# FrontPanel.net
KiCad netlist of a schematic drawn in EAGLE
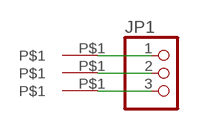
[diagram p0: schematic, sheet 1]

(export (version "E")
  (design (tool "Eeschema 10.0.6"))
  (components
    (comp (ref "JP1")
      (value "PINHD-1X3_2.54-SMD")
      (footprint "eagle-import:1X03SMD")
      (libsource (lib "eagle-import") (part "PINHD-1X3_2.54-SMD"))
    )
    (comp (ref "U$8")
      (value "TOUCHPAD")
      (footprint "eagle-import:TOUCH_FIELD_10X5")
      (libsource (lib "eagle-import") (part "TOUCHPAD"))
    )
    (comp (ref "U$9")
      (value "TOUCHPAD")
      (footprint "eagle-import:TOUCH_FIELD_10X5")
      (libsource (lib "eagle-import") (part "TOUCHPAD"))
    )
    (comp (ref "U$10")
      (value "TOUCHPAD")
      (footprint "eagle-import:TOUCH_FIELD_10X5")
      (libsource (lib "eagle-import") (part "TOUCHPAD"))
    )
  )
  (nets
    (net (code "1") (name "Net-(JP1-Pad1)") (class "Default")
      (node (ref "JP1") (pin "1") (pinfunction "1_1") (pintype "passive"))
      (node (ref "U$8") (pin "P$1") (pinfunction "P$1_P$1") (pintype "bidirectional"))
    )
    (net (code "2") (name "Net-(JP1-Pad2)") (class "Default")
      (node (ref "JP1") (pin "2") (pinfunction "2_2") (pintype "passive"))
      (node (ref "U$9") (pin "P$1") (pinfunction "P$1_P$1") (pintype "bidirectional"))
    )
    (net (code "3") (name "Net-(JP1-Pad3)") (class "Default")
      (node (ref "JP1") (pin "3") (pinfunction "3_3") (pintype "passive"))
      (node (ref "U$10") (pin "P$1") (pinfunction "P$1_P$1") (pintype "bidirectional"))
    )
  )
)
